# Relay.net
KiCad netlist of a schematic drawn in Altium Designer
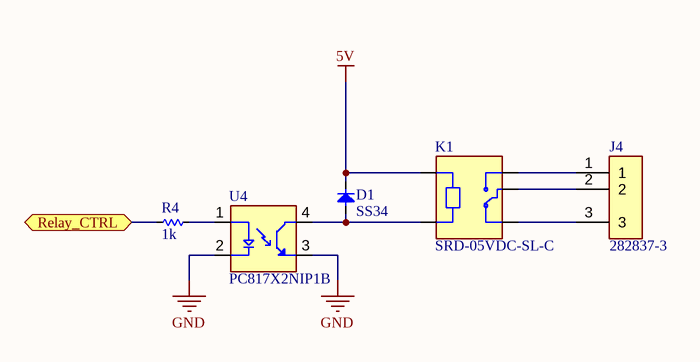
[diagram p0: Relay.SchDoc]

(export (version "E")
  (design (tool "Eeschema 10.0.6"))
  (components
    (comp (ref "D1")
      (value "SS34")
      (footprint "DO-214AC_SMA")
      (description "Default Diode")
      (fields (field (name "PUBLISHER") "Altium Limited"))
      (libsource (lib "BTL_SCHLIB") (part "Diode SMD"))
    )
    (comp (ref "J4")
      (value "282837-3")
      (footprint "TE_282837-3")
      (description "TERMI-BLOK PCB MOUNT 3P")
      (libsource (lib "BTL_SCHLIB") (part "282837-3"))
    )
    (comp (ref "K1")
      (value "SRD-05VDC-SL-C")
      (footprint "RELAY_SRD-05VDC-SL-C")
      (fields (field (name "MF") "Songle Relay"))
      (libsource (lib "BTL_SCHLIB") (part "SRD-05VDC-SL-C"))
    )
    (comp (ref "R4")
      (value "1k")
      (footprint "RES_C_1608X60")
      (description "RES")
      (libsource (lib "BTL_SCHLIB") (part "RES_SMD"))
    )
    (comp (ref "U4")
      (value "PC817X2NIP1B")
      (footprint "SOIC254P960X420-4N")
      (description "Optocoupler DC-IN 1-CH Transistor DC-OUT 4-Pin DIP SMD T/R")
      (fields (field (name "MF") "Sharp Microelectronics"))
      (libsource (lib "BTL_SCHLIB") (part "PC817X2NIP1B"))
    )
  )
  (nets
    (net (code "1") (name "/Relay_CTRL") (class "Default")
      (node (ref "R4") (pin "1") (pinfunction "1_1") (pintype "passive"))
    )
    (net (code "2") (name "5V") (class "Default")
      (node (ref "D1") (pin "1") (pinfunction "K_1") (pintype "passive"))
      (node (ref "K1") (pin "A1") (pinfunction "A1_A1") (pintype "passive"))
    )
    (net (code "3") (name "GND") (class "Default")
      (node (ref "U4") (pin "2") (pinfunction "C_2") (pintype "passive"))
      (node (ref "U4") (pin "3") (pinfunction "ET_3") (pintype "passive"))
    )
    (net (code "4") (name "Net-(D1-A)") (class "Default")
      (node (ref "D1") (pin "2") (pinfunction "A_2") (pintype "passive"))
      (node (ref "K1") (pin "A2") (pinfunction "A2_A2") (pintype "passive"))
      (node (ref "U4") (pin "4") (pinfunction "CT_4") (pintype "passive"))
    )
    (net (code "5") (name "Net-(J4-Pad1)") (class "Default")
      (node (ref "J4") (pin "1") (pinfunction "1_1") (pintype "passive"))
      (node (ref "K1") (pin "NO") (pinfunction "NO_NO") (pintype "passive"))
    )
    (net (code "6") (name "Net-(J4-Pad2)") (class "Default")
      (node (ref "J4") (pin "2") (pinfunction "2_2") (pintype "passive"))
      (node (ref "K1") (pin "COM") (pinfunction "COM_COM") (pintype "passive"))
    )
    (net (code "7") (name "Net-(J4-Pad3)") (class "Default")
      (node (ref "J4") (pin "3") (pinfunction "3_3") (pintype "passive"))
      (node (ref "K1") (pin "NC") (pinfunction "NC_NC") (pintype "passive"))
    )
    (net (code "8") (name "Net-(U4-A)") (class "Default")
      (node (ref "R4") (pin "2") (pinfunction "2_2") (pintype "passive"))
      (node (ref "U4") (pin "1") (pinfunction "A_1") (pintype "passive"))
    )
  )
)
